# OPEnS-Power-1_0_0.net
KiCad netlist of a schematic drawn in EAGLE
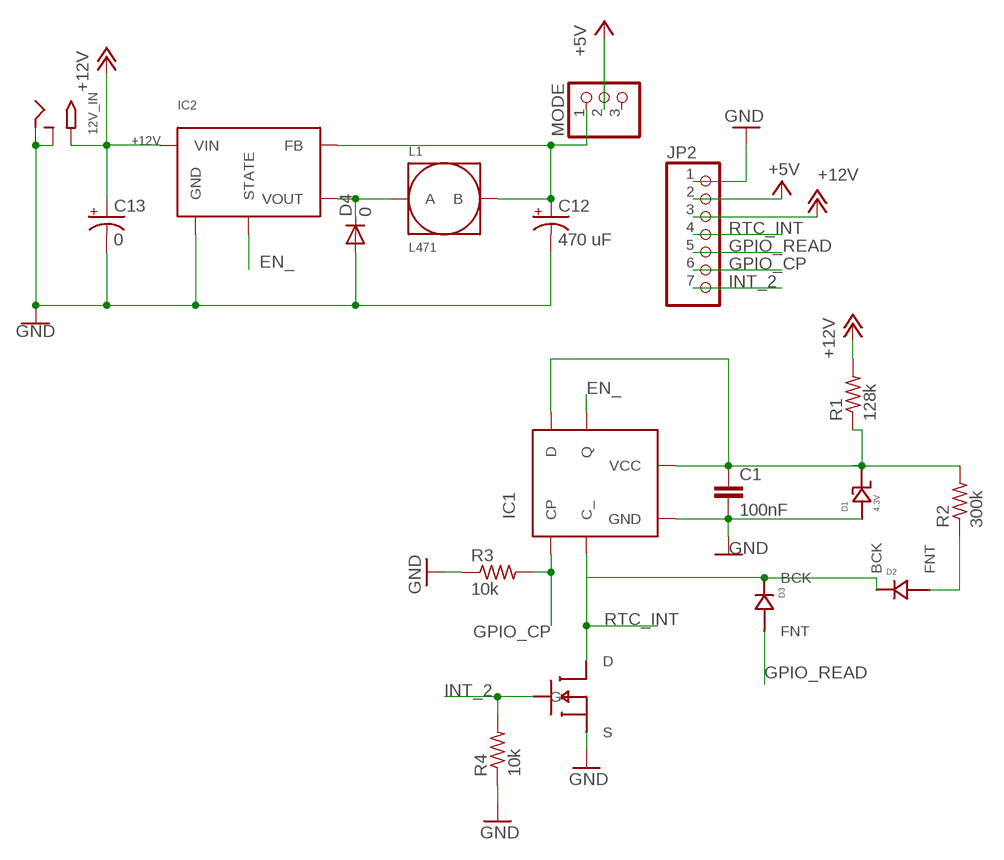
[diagram p0: schematic, sheet 1]

(export (version "E")
  (design (tool "Eeschema 10.0.6"))
  (components
    (comp (ref "12V_IN")
      (value "2.1MMJACKSMT")
      (footprint "eagle-import:DCJACK_2MM_SMT")
      (libsource (lib "eagle-import") (part "2.1MMJACKSMT"))
    )
    (comp (ref "C1")
      (value "100nF")
      (footprint "eagle-import:C0805")
      (libsource (lib "eagle-import") (part "C"))
    )
    (comp (ref "C12")
      (value "470 uF")
      (footprint "eagle-import:153CLV-0810")
      (libsource (lib "eagle-import") (part "rcl_334_CPOL-US153CLV-0810"))
    )
    (comp (ref "C13")
      (value "0")
      (footprint "eagle-import:153CLV-0505")
      (libsource (lib "eagle-import") (part "CPOL-US153CLV-0505"))
    )
    (comp (ref "D1")
      (value "4.3V")
      (footprint "eagle-import:DO-219AC")
      (libsource (lib "eagle-import") (part "ZENER-DO219"))
    )
    (comp (ref "D2")
      (value "DIODE-DO-214AC")
      (footprint "eagle-import:DIODE-DO-214AC")
      (libsource (lib "eagle-import") (part "DIODE-DO-214AC"))
    )
    (comp (ref "D3")
      (value "DIODE-DO-214AC")
      (footprint "eagle-import:DIODE-DO-214AC")
      (libsource (lib "eagle-import") (part "DIODE-DO-214AC"))
    )
    (comp (ref "D4")
      (value "0")
      (footprint "eagle-import:DO41-10")
      (libsource (lib "eagle-import") (part "1N4004"))
    )
    (comp (ref "IC1")
      (value "NC7SZ175")
      (footprint "eagle-import:SC70")
      (libsource (lib "eagle-import") (part "NC7SZ175"))
    )
    (comp (ref "IC2")
      (value "LM2575")
      (footprint "eagle-import:TO-263")
      (libsource (lib "eagle-import") (part "LM2575"))
    )
    (comp (ref "JP2")
      (value "PINHD-1X7")
      (footprint "eagle-import:1X07")
      (libsource (lib "eagle-import") (part "PINHD-1X7"))
    )
    (comp (ref "L1")
      (value "L471")
      (footprint "eagle-import:12-12")
      (libsource (lib "eagle-import") (part "L471"))
    )
    (comp (ref "MODE")
      (value "PINHD-1X3")
      (footprint "eagle-import:1X03")
      (libsource (lib "eagle-import") (part "PINHD-1X3"))
    )
    (comp (ref "Q1")
      (value "MOSFET-SOT23F")
      (footprint "eagle-import:SOT-23F")
      (libsource (lib "eagle-import") (part "MOSFET-SOT23F"))
    )
    (comp (ref "R1")
      (value "128k")
      (footprint "eagle-import:R0805")
      (libsource (lib "eagle-import") (part "R-US_R0805"))
    )
    (comp (ref "R2")
      (value "300k")
      (footprint "eagle-import:R0805")
      (libsource (lib "eagle-import") (part "R-US_R0805"))
    )
    (comp (ref "R3")
      (value "10k")
      (footprint "eagle-import:R0805")
      (libsource (lib "eagle-import") (part "R-US_R0805"))
    )
    (comp (ref "R4")
      (value "10k")
      (footprint "eagle-import:R0805")
      (libsource (lib "eagle-import") (part "R-US_R0805"))
    )
  )
  (nets
    (net (code "1") (name "+5V") (class "Default")
      (node (ref "JP2") (pin "2") (pinfunction "2_2") (pintype "passive"))
      (node (ref "MODE") (pin "2") (pinfunction "2_2") (pintype "passive"))
    )
    (net (code "2") (name "+12V") (class "Default")
      (node (ref "12V_IN") (pin "PWR2") (pinfunction "TIP_PWR2") (pintype "bidirectional"))
      (node (ref "C13") (pin "+") (pinfunction "+_+") (pintype "passive"))
      (node (ref "IC2") (pin "VIN") (pinfunction "VIN_VIN") (pintype "bidirectional"))
      (node (ref "JP2") (pin "3") (pinfunction "3_3") (pintype "passive"))
      (node (ref "R1") (pin "2") (pinfunction "2_2") (pintype "passive"))
    )
    (net (code "3") (name "/EN_") (class "Default")
      (node (ref "IC1") (pin "Q") (pinfunction "Q_Q") (pintype "bidirectional"))
      (node (ref "IC2") (pin "STATE") (pinfunction "STATE_STATE") (pintype "bidirectional"))
    )
    (net (code "4") (name "/GPIO_CP") (class "Default")
      (node (ref "IC1") (pin "CP") (pinfunction "CP_CP") (pintype "bidirectional"))
      (node (ref "JP2") (pin "6") (pinfunction "6_6") (pintype "passive"))
      (node (ref "R3") (pin "2") (pinfunction "2_2") (pintype "passive"))
    )
    (net (code "5") (name "/GPIO_READ") (class "Default")
      (node (ref "D3") (pin "FNT") (pinfunction "FNT_FNT") (pintype "bidirectional"))
      (node (ref "JP2") (pin "5") (pinfunction "5_5") (pintype "passive"))
    )
    (net (code "6") (name "/INT_2") (class "Default")
      (node (ref "JP2") (pin "7") (pinfunction "7_7") (pintype "passive"))
      (node (ref "Q1") (pin "G") (pinfunction "G_G") (pintype "bidirectional"))
      (node (ref "R4") (pin "2") (pinfunction "2_2") (pintype "passive"))
    )
    (net (code "7") (name "/RTC_INT") (class "Default")
      (node (ref "D2") (pin "BCK") (pinfunction "BCK_BCK") (pintype "bidirectional"))
      (node (ref "D3") (pin "BCK") (pinfunction "BCK_BCK") (pintype "bidirectional"))
      (node (ref "IC1") (pin "C_") (pinfunction "C__C_") (pintype "bidirectional"))
      (node (ref "JP2") (pin "4") (pinfunction "4_4") (pintype "passive"))
      (node (ref "Q1") (pin "D") (pinfunction "D_D") (pintype "bidirectional"))
    )
    (net (code "8") (name "GND") (class "Default")
      (node (ref "12V_IN") (pin "GND") (pinfunction "RING_GND") (pintype "bidirectional"))
      (node (ref "12V_IN") (pin "GNDBREAK") (pinfunction "RING_SW_GNDBREAK") (pintype "bidirectional"))
      (node (ref "C1") (pin "2") (pinfunction "2_2") (pintype "passive"))
      (node (ref "C12") (pin "-") (pinfunction "-_-") (pintype "passive"))
      (node (ref "C13") (pin "-") (pinfunction "-_-") (pintype "passive"))
      (node (ref "D1") (pin "BCK") (pinfunction "BCK_BCK") (pintype "bidirectional"))
      (node (ref "D4") (pin "A") (pinfunction "A_A") (pintype "passive"))
      (node (ref "IC1") (pin "GND") (pinfunction "GND_GND") (pintype "bidirectional"))
      (node (ref "IC2") (pin "GND") (pinfunction "GND_GND") (pintype "bidirectional"))
      (node (ref "JP2") (pin "1") (pinfunction "1_1") (pintype "passive"))
      (node (ref "Q1") (pin "S") (pinfunction "S_S") (pintype "bidirectional"))
      (node (ref "R3") (pin "1") (pinfunction "1_1") (pintype "passive"))
      (node (ref "R4") (pin "1") (pinfunction "1_1") (pintype "passive"))
    )
    (net (code "9") (name "Net-(C1-Pad1)") (class "Default")
      (node (ref "C1") (pin "1") (pinfunction "1_1") (pintype "passive"))
      (node (ref "D1") (pin "FNT") (pinfunction "FNT_FNT") (pintype "bidirectional"))
      (node (ref "IC1") (pin "D") (pinfunction "D_D") (pintype "bidirectional"))
      (node (ref "IC1") (pin "VCC") (pinfunction "VCC_VCC") (pintype "bidirectional"))
      (node (ref "R1") (pin "1") (pinfunction "1_1") (pintype "passive"))
      (node (ref "R2") (pin "2") (pinfunction "2_2") (pintype "passive"))
    )
    (net (code "10") (name "Net-(C12-Pad+)") (class "Default")
      (node (ref "C12") (pin "+") (pinfunction "+_+") (pintype "passive"))
      (node (ref "IC2") (pin "FB") (pinfunction "FB_FB") (pintype "bidirectional"))
      (node (ref "L1") (pin "B") (pinfunction "B_B") (pintype "bidirectional"))
      (node (ref "MODE") (pin "1") (pinfunction "1_1") (pintype "passive"))
    )
    (net (code "11") (name "Net-(D2-PadFNT)") (class "Default")
      (node (ref "D2") (pin "FNT") (pinfunction "FNT_FNT") (pintype "bidirectional"))
      (node (ref "R2") (pin "1") (pinfunction "1_1") (pintype "passive"))
    )
    (net (code "12") (name "Net-(D4-PadC)") (class "Default")
      (node (ref "D4") (pin "C") (pinfunction "C_C") (pintype "passive"))
      (node (ref "IC2") (pin "VOUT") (pinfunction "VOUT_VOUT") (pintype "bidirectional"))
      (node (ref "L1") (pin "A") (pinfunction "A_A") (pintype "bidirectional"))
    )
    (net (code "13") (name "unconnected-(MODE-Pad3)") (class "Default")
      (node (ref "MODE") (pin "3") (pinfunction "3_3") (pintype "passive"))
    )
  )
)
